# Schematic.net
KiCad netlist of a schematic drawn in EAGLE
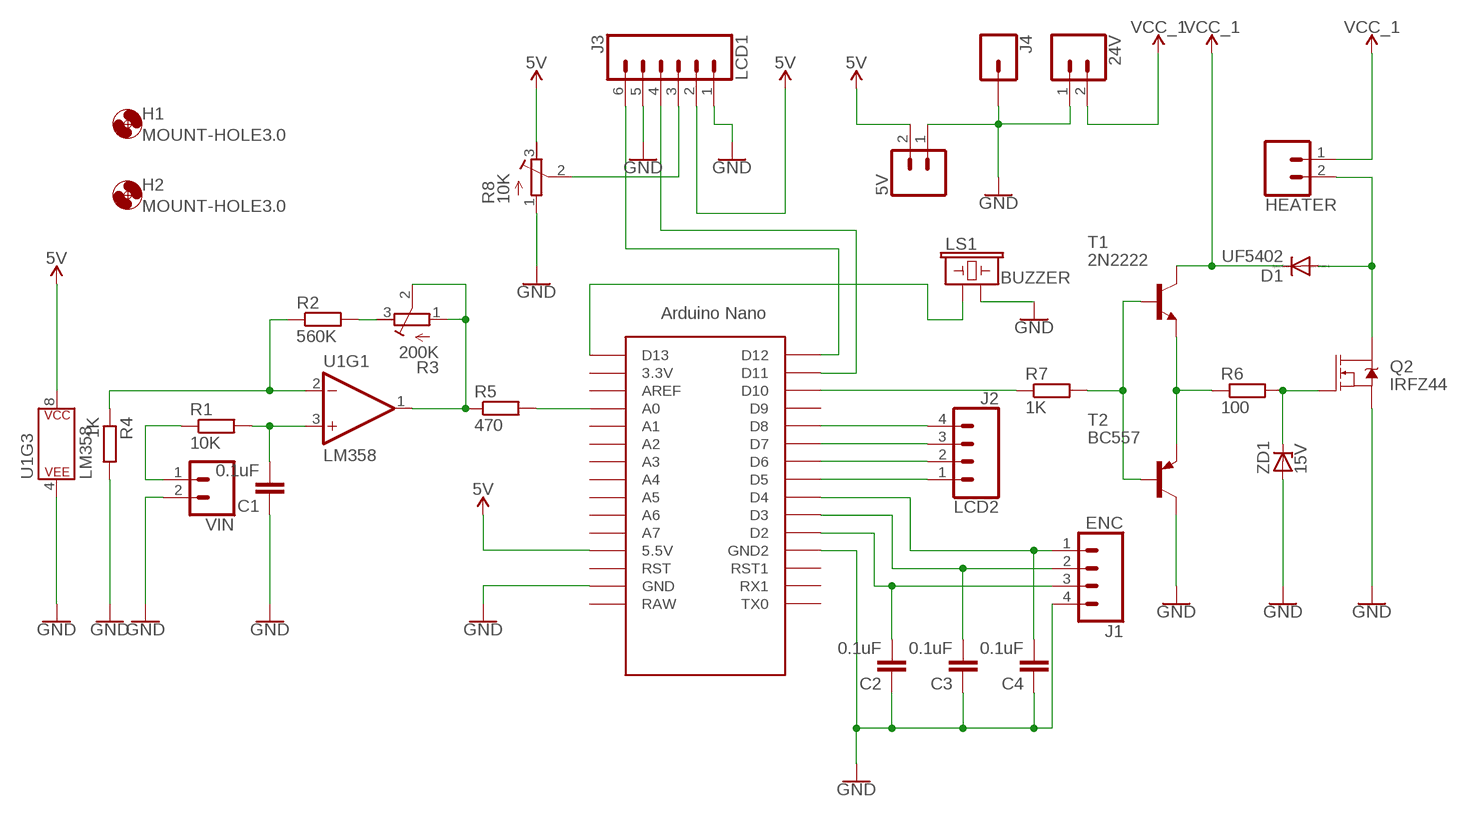
[diagram p0: schematic, sheet 1]

(export (version "E")
  (design (tool "Eeschema 10.0.6"))
  (components
    (comp (ref "5V")
      (value "CONN_025MM")
      (footprint "eagle-import:SCREWTERMINAL-5MM-2")
      (libsource (lib "eagle-import") (part "CONN_025MM"))
    )
    (comp (ref "24V")
      (value "CONN_025MM")
      (footprint "eagle-import:SCREWTERMINAL-5MM-2")
      (libsource (lib "eagle-import") (part "CONN_025MM"))
    )
    (comp (ref "C1")
      (value "0.1uF")
      (footprint "eagle-import:C025-024X044")
      (libsource (lib "eagle-import") (part "C-EU025-024X044"))
    )
    (comp (ref "C2")
      (value "0.1uF")
      (footprint "eagle-import:C025-024X044")
      (libsource (lib "eagle-import") (part "C-EU025-024X044"))
    )
    (comp (ref "C3")
      (value "0.1uF")
      (footprint "eagle-import:C025-024X044")
      (libsource (lib "eagle-import") (part "C-EU025-024X044"))
    )
    (comp (ref "C4")
      (value "0.1uF")
      (footprint "eagle-import:C025-024X044")
      (libsource (lib "eagle-import") (part "C-EU025-024X044"))
    )
    (comp (ref "D1")
      (value "UF5402")
      (footprint "eagle-import:DO41-10")
      (libsource (lib "eagle-import") (part "UF4003"))
    )
    (comp (ref "H1")
      (value "MOUNT-HOLE3.0")
      (footprint "eagle-import:3,0")
      (libsource (lib "eagle-import") (part "MOUNT-HOLE3.0"))
    )
    (comp (ref "H2")
      (value "MOUNT-HOLE3.0")
      (footprint "eagle-import:3,0")
      (libsource (lib "eagle-import") (part "MOUNT-HOLE3.0"))
    )
    (comp (ref "HEATER")
      (value "CONN_02PTH4")
      (footprint "eagle-import:1X02_XTRA_BIG")
      (libsource (lib "eagle-import") (part "CONN_02PTH4"))
    )
    (comp (ref "J1")
      (value "ENC")
      (footprint "eagle-import:1X04_LONGPADS")
      (libsource (lib "eagle-import") (part "CONN_04LONGPADS"))
    )
    (comp (ref "J2")
      (value "LCD2")
      (footprint "eagle-import:1X04_LONGPADS")
      (libsource (lib "eagle-import") (part "CONN_04LONGPADS"))
    )
    (comp (ref "J3")
      (value "LCD1")
      (footprint "eagle-import:1X06_LONGPADS")
      (libsource (lib "eagle-import") (part "CONN_06LONGPADS"))
    )
    (comp (ref "J4")
      (value "CONN_01PTH_2MM")
      (footprint "eagle-import:1X01_2MM")
      (libsource (lib "eagle-import") (part "CONN_01PTH_2MM"))
    )
    (comp (ref "LS1")
      (value "BUZZER")
      (footprint "eagle-import:BUZZER-12MM-NS")
      (libsource (lib "eagle-import") (part "BUZZER-PTH_NO_SILK"))
    )
    (comp (ref "Q2")
      (value "IRFZ44")
      (footprint "eagle-import:TO220V")
      (libsource (lib "eagle-import") (part "MOSFET-NCH-FQP30N06L"))
    )
    (comp (ref "R1")
      (value "10K")
      (footprint "eagle-import:0204_7")
      (libsource (lib "eagle-import") (part "R-EU_0204/7"))
    )
    (comp (ref "R2")
      (value "560K")
      (footprint "eagle-import:0204_7")
      (libsource (lib "eagle-import") (part "R-EU_0204/7"))
    )
    (comp (ref "R3")
      (value "200K")
      (footprint "eagle-import:RTRIM64W")
      (libsource (lib "eagle-import") (part "R-TRIMM64W"))
    )
    (comp (ref "R4")
      (value "1K")
      (footprint "eagle-import:0204_7")
      (libsource (lib "eagle-import") (part "R-EU_0204/7"))
    )
    (comp (ref "R5")
      (value "470")
      (footprint "eagle-import:0204_7")
      (libsource (lib "eagle-import") (part "R-EU_0204/7"))
    )
    (comp (ref "R6")
      (value "100")
      (footprint "eagle-import:0204_7")
      (libsource (lib "eagle-import") (part "R-EU_0204/7"))
    )
    (comp (ref "R7")
      (value "1K")
      (footprint "eagle-import:0204_7")
      (libsource (lib "eagle-import") (part "R-EU_0204/7"))
    )
    (comp (ref "R8")
      (value "10K")
      (footprint "eagle-import:RTRIM64W")
      (libsource (lib "eagle-import") (part "R-TRIMM64W"))
    )
    (comp (ref "T1")
      (value "2N2222")
      (footprint "eagle-import:TO92-EBC-OVAL")
      (libsource (lib "eagle-import") (part "2N2222"))
    )
    (comp (ref "T2")
      (value "BC557")
      (footprint "eagle-import:TO92")
      (libsource (lib "eagle-import") (part "BC557"))
    )
    (comp (ref "U$1")
      (value "NANO")
      (footprint "eagle-import:NANO")
      (libsource (lib "eagle-import") (part "NANO"))
    )
    (comp (ref "U1")
      (value "LM358")
      (footprint "eagle-import:DIP08")
      (libsource (lib "eagle-import") (part "LM358"))
    )
    (comp (ref "VIN")
      (value "CONN_02POLAR_LOCK")
      (footprint "eagle-import:MOLEX-1X2_LOCK")
      (libsource (lib "eagle-import") (part "CONN_02POLAR_LOCK"))
    )
    (comp (ref "ZD1")
      (value "15V")
      (footprint "eagle-import:DO41Z10")
      (libsource (lib "eagle-import") (part "1N4728"))
    )
  )
  (nets
    (net (code "1") (name "5V") (class "Default")
      (node (ref "5V") (pin "2") (pinfunction "2_2") (pintype "passive"))
      (node (ref "J3") (pin "2") (pinfunction "2_2") (pintype "passive"))
      (node (ref "R8") (pin "3") (pinfunction "E_3") (pintype "passive"))
      (node (ref "U$1") (pin "5V") (pinfunction "5.5V_5V") (pintype "bidirectional"))
      (node (ref "U1") (pin "8") (pinfunction "P$V+_8") (pintype "bidirectional"))
    )
    (net (code "2") (name "GND") (class "Default")
      (node (ref "24V") (pin "1") (pinfunction "1_1") (pintype "passive"))
      (node (ref "5V") (pin "1") (pinfunction "1_1") (pintype "passive"))
      (node (ref "C1") (pin "1") (pinfunction "1_1") (pintype "passive"))
      (node (ref "C2") (pin "1") (pinfunction "1_1") (pintype "passive"))
      (node (ref "C3") (pin "1") (pinfunction "1_1") (pintype "passive"))
      (node (ref "C4") (pin "1") (pinfunction "1_1") (pintype "passive"))
      (node (ref "J1") (pin "4") (pinfunction "4_4") (pintype "passive"))
      (node (ref "J3") (pin "1") (pinfunction "1_1") (pintype "passive"))
      (node (ref "J3") (pin "5") (pinfunction "5_5") (pintype "passive"))
      (node (ref "J4") (pin "1") (pinfunction "1_1") (pintype "passive"))
      (node (ref "LS1") (pin "-") (pinfunction "2_-") (pintype "passive"))
      (node (ref "Q2") (pin "3") (pinfunction "S_3") (pintype "bidirectional"))
      (node (ref "R4") (pin "2") (pinfunction "2_2") (pintype "passive"))
      (node (ref "R8") (pin "1") (pinfunction "A_1") (pintype "passive"))
      (node (ref "T2") (pin "3") (pinfunction "C_3") (pintype "passive"))
      (node (ref "U$1") (pin "GND") (pinfunction "GND_GND") (pintype "bidirectional"))
      (node (ref "U$1") (pin "GND1") (pinfunction "GND2_GND1") (pintype "bidirectional"))
      (node (ref "U1") (pin "4") (pinfunction "P$V-_4") (pintype "bidirectional"))
      (node (ref "VIN") (pin "2") (pinfunction "2_2") (pintype "passive"))
      (node (ref "ZD1") (pin "A") (pinfunction "A_A") (pintype "passive"))
    )
    (net (code "3") (name "Net-(C2-Pad2)") (class "Default")
      (node (ref "C2") (pin "2") (pinfunction "2_2") (pintype "passive"))
      (node (ref "J1") (pin "3") (pinfunction "3_3") (pintype "passive"))
      (node (ref "U$1") (pin "D2") (pinfunction "D2_D2") (pintype "bidirectional"))
    )
    (net (code "4") (name "Net-(C3-Pad2)") (class "Default")
      (node (ref "C3") (pin "2") (pinfunction "2_2") (pintype "passive"))
      (node (ref "J1") (pin "2") (pinfunction "2_2") (pintype "passive"))
      (node (ref "U$1") (pin "D3") (pinfunction "D3_D3") (pintype "bidirectional"))
    )
    (net (code "5") (name "Net-(C4-Pad2)") (class "Default")
      (node (ref "C4") (pin "2") (pinfunction "2_2") (pintype "passive"))
      (node (ref "J1") (pin "1") (pinfunction "1_1") (pintype "passive"))
      (node (ref "U$1") (pin "D4") (pinfunction "D4_D4") (pintype "bidirectional"))
    )
    (net (code "6") (name "Net-(J2-Pad1)") (class "Default")
      (node (ref "J2") (pin "1") (pinfunction "1_1") (pintype "passive"))
      (node (ref "U$1") (pin "D5") (pinfunction "D5_D5") (pintype "bidirectional"))
    )
    (net (code "7") (name "Net-(J2-Pad2)") (class "Default")
      (node (ref "J2") (pin "2") (pinfunction "2_2") (pintype "passive"))
      (node (ref "U$1") (pin "D6") (pinfunction "D6_D6") (pintype "bidirectional"))
    )
    (net (code "8") (name "Net-(J2-Pad3)") (class "Default")
      (node (ref "J2") (pin "3") (pinfunction "3_3") (pintype "passive"))
      (node (ref "U$1") (pin "D7") (pinfunction "D7_D7") (pintype "bidirectional"))
    )
    (net (code "9") (name "Net-(J2-Pad4)") (class "Default")
      (node (ref "J2") (pin "4") (pinfunction "4_4") (pintype "passive"))
      (node (ref "U$1") (pin "D8") (pinfunction "D8_D8") (pintype "bidirectional"))
    )
    (net (code "10") (name "Net-(J3-Pad4)") (class "Default")
      (node (ref "J3") (pin "4") (pinfunction "4_4") (pintype "passive"))
      (node (ref "U$1") (pin "D11") (pinfunction "D11_D11") (pintype "bidirectional"))
    )
    (net (code "11") (name "Net-(J3-Pad6)") (class "Default")
      (node (ref "J3") (pin "6") (pinfunction "6_6") (pintype "passive"))
      (node (ref "U$1") (pin "D12") (pinfunction "D12_D12") (pintype "bidirectional"))
    )
    (net (code "12") (name "Net-(LS1-1)") (class "Default")
      (node (ref "LS1") (pin "+") (pinfunction "1_+") (pintype "passive"))
      (node (ref "U$1") (pin "D13") (pinfunction "D13_D13") (pintype "bidirectional"))
    )
    (net (code "13") (name "Net-(Q2-D)") (class "Default")
      (node (ref "D1") (pin "A") (pinfunction "A_A") (pintype "passive"))
      (node (ref "HEATER") (pin "2") (pinfunction "2_2") (pintype "passive"))
      (node (ref "Q2") (pin "2") (pinfunction "D_2") (pintype "bidirectional"))
    )
    (net (code "14") (name "Net-(Q2-G)") (class "Default")
      (node (ref "Q2") (pin "1") (pinfunction "G_1") (pintype "bidirectional"))
      (node (ref "R6") (pin "2") (pinfunction "2_2") (pintype "passive"))
      (node (ref "ZD1") (pin "C") (pinfunction "C_C") (pintype "passive"))
    )
    (net (code "15") (name "Net-(R1-Pad1)") (class "Default")
      (node (ref "R1") (pin "1") (pinfunction "1_1") (pintype "passive"))
      (node (ref "VIN") (pin "1") (pinfunction "1_1") (pintype "passive"))
    )
    (net (code "16") (name "Net-(R3-A)") (class "Default")
      (node (ref "R3") (pin "1") (pinfunction "A_1") (pintype "passive"))
      (node (ref "R3") (pin "2") (pinfunction "S_2") (pintype "passive"))
      (node (ref "R5") (pin "1") (pinfunction "1_1") (pintype "passive"))
      (node (ref "U1") (pin "1") (pinfunction "OUT_1") (pintype "output"))
    )
    (net (code "17") (name "Net-(R3-E)") (class "Default")
      (node (ref "R2") (pin "2") (pinfunction "2_2") (pintype "passive"))
      (node (ref "R3") (pin "3") (pinfunction "E_3") (pintype "passive"))
    )
    (net (code "18") (name "Net-(R5-Pad2)") (class "Default")
      (node (ref "R5") (pin "2") (pinfunction "2_2") (pintype "passive"))
      (node (ref "U$1") (pin "A0") (pinfunction "A0_A0") (pintype "bidirectional"))
    )
    (net (code "19") (name "Net-(R7-Pad1)") (class "Default")
      (node (ref "R7") (pin "1") (pinfunction "1_1") (pintype "passive"))
      (node (ref "U$1") (pin "D10") (pinfunction "D10_D10") (pintype "bidirectional"))
    )
    (net (code "20") (name "Net-(R8-S)") (class "Default")
      (node (ref "J3") (pin "3") (pinfunction "3_3") (pintype "passive"))
      (node (ref "R8") (pin "2") (pinfunction "S_2") (pintype "passive"))
    )
    (net (code "21") (name "Net-(T2-B)") (class "Default")
      (node (ref "R7") (pin "2") (pinfunction "2_2") (pintype "passive"))
      (node (ref "T1") (pin "B") (pinfunction "B_B") (pintype "passive"))
      (node (ref "T2") (pin "2") (pinfunction "B_2") (pintype "passive"))
    )
    (net (code "22") (name "Net-(T2-E)") (class "Default")
      (node (ref "R6") (pin "1") (pinfunction "1_1") (pintype "passive"))
      (node (ref "T1") (pin "E") (pinfunction "E_E") (pintype "passive"))
      (node (ref "T2") (pin "1") (pinfunction "E_1") (pintype "passive"))
    )
    (net (code "23") (name "Net-(U1A-+IN)") (class "Default")
      (node (ref "C1") (pin "2") (pinfunction "2_2") (pintype "passive"))
      (node (ref "R1") (pin "2") (pinfunction "2_2") (pintype "passive"))
      (node (ref "U1") (pin "3") (pinfunction "+IN_3") (pintype "input"))
    )
    (net (code "24") (name "Net-(U1A--IN)") (class "Default")
      (node (ref "R2") (pin "1") (pinfunction "1_1") (pintype "passive"))
      (node (ref "R4") (pin "1") (pinfunction "1_1") (pintype "passive"))
      (node (ref "U1") (pin "2") (pinfunction "-IN_2") (pintype "input"))
    )
    (net (code "25") (name "VCC_1") (class "Default")
      (node (ref "24V") (pin "2") (pinfunction "2_2") (pintype "passive"))
      (node (ref "D1") (pin "C") (pinfunction "C_C") (pintype "passive"))
      (node (ref "HEATER") (pin "1") (pinfunction "1_1") (pintype "passive"))
      (node (ref "T1") (pin "C") (pinfunction "C_C") (pintype "passive"))
    )
    (net (code "26") (name "unconnected-(U$1-Pad3.3V)") (class "Default")
      (node (ref "U$1") (pin "3.3V") (pinfunction "3.3V_3.3V") (pintype "bidirectional"))
    )
    (net (code "27") (name "unconnected-(U$1-PadA1)") (class "Default")
      (node (ref "U$1") (pin "A1") (pinfunction "A1_A1") (pintype "bidirectional"))
    )
    (net (code "28") (name "unconnected-(U$1-PadA2)") (class "Default")
      (node (ref "U$1") (pin "A2") (pinfunction "A2_A2") (pintype "bidirectional"))
    )
    (net (code "29") (name "unconnected-(U$1-PadA3)") (class "Default")
      (node (ref "U$1") (pin "A3") (pinfunction "A3_A3") (pintype "bidirectional"))
    )
    (net (code "30") (name "unconnected-(U$1-PadA4)") (class "Default")
      (node (ref "U$1") (pin "A4") (pinfunction "A4_A4") (pintype "bidirectional"))
    )
    (net (code "31") (name "unconnected-(U$1-PadA5)") (class "Default")
      (node (ref "U$1") (pin "A5") (pinfunction "A5_A5") (pintype "bidirectional"))
    )
    (net (code "32") (name "unconnected-(U$1-PadA6)") (class "Default")
      (node (ref "U$1") (pin "A6") (pinfunction "A6_A6") (pintype "bidirectional"))
    )
    (net (code "33") (name "unconnected-(U$1-PadA7)") (class "Default")
      (node (ref "U$1") (pin "A7") (pinfunction "A7_A7") (pintype "bidirectional"))
    )
    (net (code "34") (name "unconnected-(U$1-PadAREF)") (class "Default")
      (node (ref "U$1") (pin "AREF") (pinfunction "AREF_AREF") (pintype "bidirectional"))
    )
    (net (code "35") (name "unconnected-(U$1-PadD9)") (class "Default")
      (node (ref "U$1") (pin "D9") (pinfunction "D9_D9") (pintype "bidirectional"))
    )
    (net (code "36") (name "unconnected-(U$1-PadICSP1)") (class "Default")
      (node (ref "U$1") (pin "ICSP1") (pinfunction "ICSP1_ICSP1") (pintype "bidirectional"))
    )
    (net (code "37") (name "unconnected-(U$1-PadICSP2)") (class "Default")
      (node (ref "U$1") (pin "ICSP2") (pinfunction "ICSP2_ICSP2") (pintype "bidirectional"))
    )
    (net (code "38") (name "unconnected-(U$1-PadICSP3)") (class "Default")
      (node (ref "U$1") (pin "ICSP3") (pinfunction "ICSP3_ICSP3") (pintype "bidirectional"))
    )
    (net (code "39") (name "unconnected-(U$1-PadICSP4)") (class "Default")
      (node (ref "U$1") (pin "ICSP4") (pinfunction "ICSP4_ICSP4") (pintype "bidirectional"))
    )
    (net (code "40") (name "unconnected-(U$1-PadICSP5)") (class "Default")
      (node (ref "U$1") (pin "ICSP5") (pinfunction "ICSP5_ICSP5") (pintype "bidirectional"))
    )
    (net (code "41") (name "unconnected-(U$1-PadICSP6)") (class "Default")
      (node (ref "U$1") (pin "ICSP6") (pinfunction "ICSP6_ICSP6") (pintype "bidirectional"))
    )
    (net (code "42") (name "unconnected-(U$1-PadRAW)") (class "Default")
      (node (ref "U$1") (pin "RAW") (pinfunction "RAW_RAW") (pintype "bidirectional"))
    )
    (net (code "43") (name "unconnected-(U$1-PadRST)") (class "Default")
      (node (ref "U$1") (pin "RST") (pinfunction "RST_RST") (pintype "bidirectional"))
    )
    (net (code "44") (name "unconnected-(U$1-PadRST1)") (class "Default")
      (node (ref "U$1") (pin "RST1") (pinfunction "RST1_RST1") (pintype "bidirectional"))
    )
    (net (code "45") (name "unconnected-(U$1-PadRX1)") (class "Default")
      (node (ref "U$1") (pin "RX1") (pinfunction "RX1_RX1") (pintype "bidirectional"))
    )
    (net (code "46") (name "unconnected-(U$1-PadTX0)") (class "Default")
      (node (ref "U$1") (pin "TX0") (pinfunction "TX0_TX0") (pintype "bidirectional"))
    )
  )
)
